# sdram_uni.net
KiCad netlist of a schematic drawn in Altium Designer
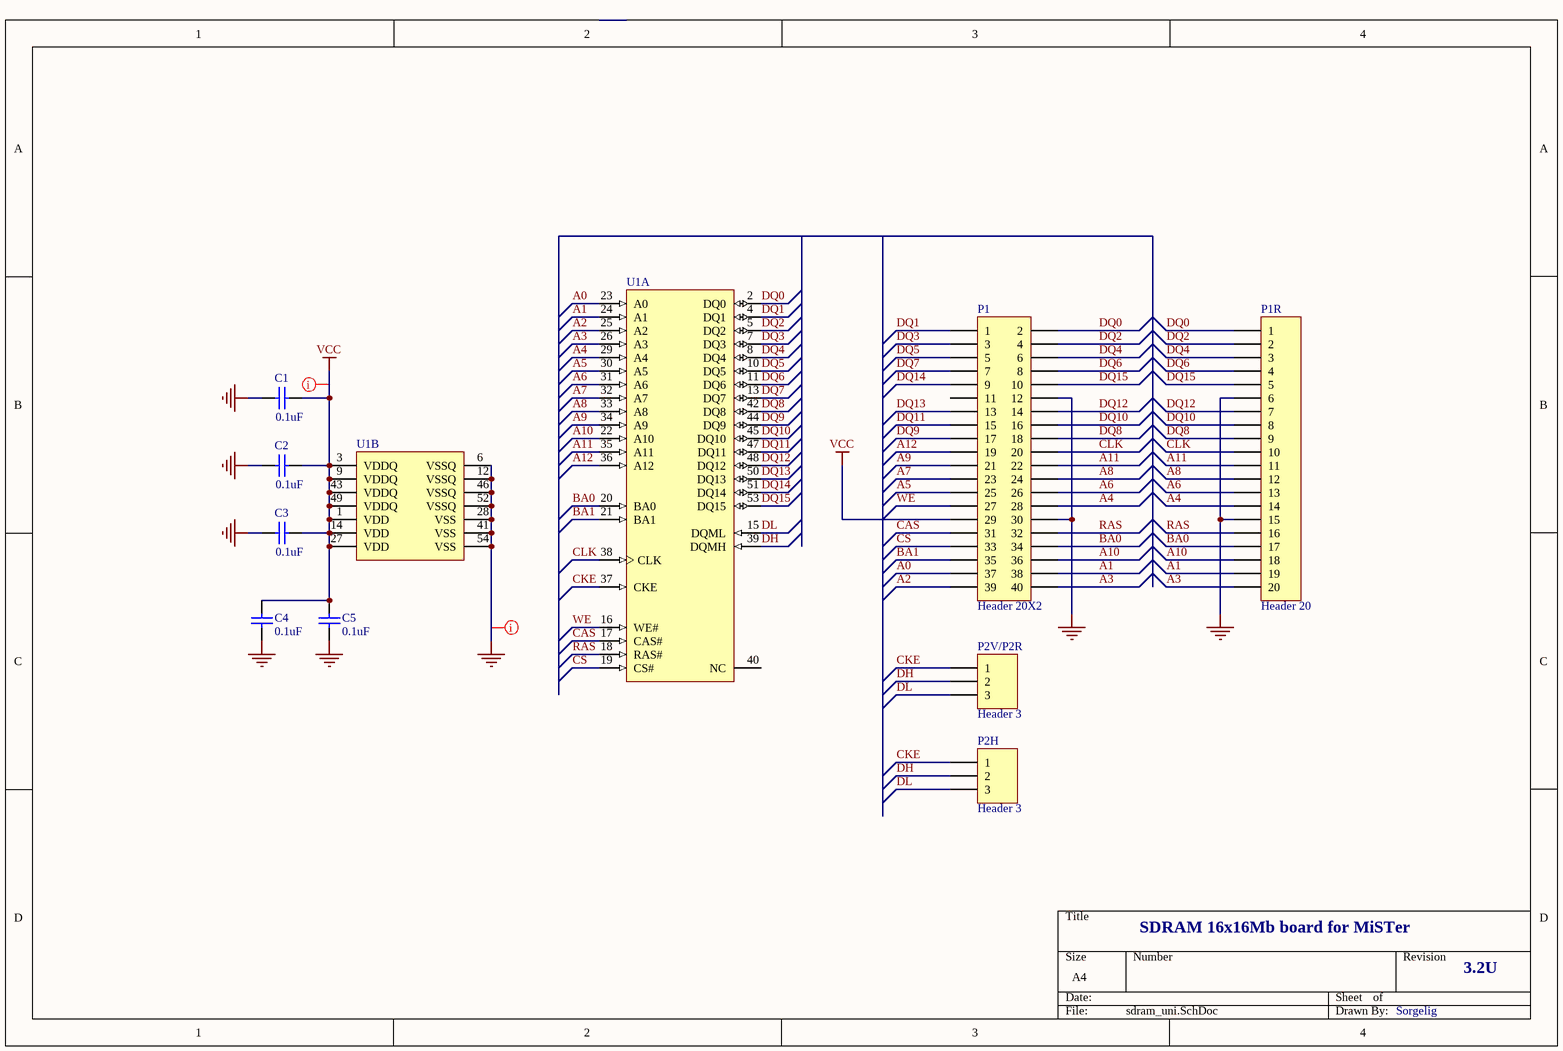
[diagram p0: sdram_uni.SchDoc]

(export (version "E")
  (design (tool "Eeschema 10.0.6"))
  (components
    (comp (ref "C1")
      (value "0.1uF")
      (footprint "C0805")
      (description "Ceramic Chip Capacitor - Standard")
      (fields (field (name "Comment") "C0805") (field (name "PUBLISHER") "Altium Limited"))
      (libsource (lib "lib") (part "C0805"))
    )
    (comp (ref "C2")
      (value "0.1uF")
      (footprint "C0805")
      (description "Ceramic Chip Capacitor - Standard")
      (fields (field (name "Comment") "C0805") (field (name "PUBLISHER") "Altium Limited"))
      (libsource (lib "lib") (part "C0805"))
    )
    (comp (ref "C3")
      (value "0.1uF")
      (footprint "C0805")
      (description "Ceramic Chip Capacitor - Standard")
      (fields (field (name "Comment") "+") (field (name "PUBLISHER") "Altium Limited"))
      (libsource (lib "lib") (part "C0805"))
    )
    (comp (ref "C4")
      (value "0.1uF")
      (footprint "C0805")
      (description "Ceramic Chip Capacitor - Standard")
      (fields (field (name "Comment") "C0805") (field (name "PUBLISHER") "Altium Limited"))
      (libsource (lib "lib") (part "C0805"))
    )
    (comp (ref "C5")
      (value "0.1uF")
      (footprint "C0805")
      (description "Ceramic Chip Capacitor - Standard")
      (fields (field (name "Comment") "+") (field (name "PUBLISHER") "Altium Limited"))
      (libsource (lib "lib") (part "C0805"))
    )
    (comp (ref "P1")
      (value "Header 20X2")
      (footprint "HDR20x2_90")
      (description "Header, 20-Pin, Dual row")
      (fields (field (name "PUBLISHER") "Altium Limited"))
      (libsource (lib "Miscellaneous Connectors") (part "Header 20X2"))
    )
    (comp (ref "P1R")
      (value "Header 20")
      (footprint "HDR1X20")
      (description "Header, 20-Pin")
      (fields (field (name "PUBLISHER") "Altium Limited"))
      (libsource (lib "Miscellaneous Connectors") (part "Header 20"))
    )
    (comp (ref "P2H")
      (value "Header 3")
      (footprint "HDR1X3")
      (description "Header, 3-Pin")
      (fields (field (name "PUBLISHER") "Altium Limited"))
      (libsource (lib "Miscellaneous Connectors") (part "Header 3"))
    )
    (comp (ref "P2V/P2R")
      (value "Header 3")
      (footprint "HDR1X3")
      (description "Header, 3-Pin")
      (fields (field (name "PUBLISHER") "Altium Limited"))
      (libsource (lib "Miscellaneous Connectors") (part "Header 3"))
    )
    (comp (ref "U1")
      (value "~")
      (footprint "TSOP54")
      (description "256Mb SDR SDRAM, 16Mb x 16, 6ns, 3.3V, 54-Pin TSOP")
      (fields (field (name "VOLTAGE") "3.3V ") (field (name "MANUFACTURER") "Micron"))
      (libsource (lib "lib") (part "AS4C16M16SA-6TCN"))
    )
  )
  (nets
    (net (code "1") (name "/A0") (class "Default")
      (node (ref "P1") (pin "37") (pinfunction "37_37") (pintype "passive"))
      (node (ref "U1") (pin "23") (pinfunction "A0_23") (pintype "input"))
    )
    (net (code "2") (name "/A1") (class "Default")
      (node (ref "P1") (pin "38") (pinfunction "38_38") (pintype "passive"))
      (node (ref "P1R") (pin "19") (pinfunction "19_19") (pintype "passive"))
      (node (ref "U1") (pin "24") (pinfunction "A1_24") (pintype "input"))
    )
    (net (code "3") (name "/A2") (class "Default")
      (node (ref "P1") (pin "39") (pinfunction "39_39") (pintype "passive"))
      (node (ref "U1") (pin "25") (pinfunction "A2_25") (pintype "input"))
    )
    (net (code "4") (name "/A3") (class "Default")
      (node (ref "P1") (pin "40") (pinfunction "40_40") (pintype "passive"))
      (node (ref "P1R") (pin "20") (pinfunction "20_20") (pintype "passive"))
      (node (ref "U1") (pin "26") (pinfunction "A3_26") (pintype "input"))
    )
    (net (code "5") (name "/A4") (class "Default")
      (node (ref "P1") (pin "28") (pinfunction "28_28") (pintype "passive"))
      (node (ref "P1R") (pin "14") (pinfunction "14_14") (pintype "passive"))
      (node (ref "U1") (pin "29") (pinfunction "A4_29") (pintype "input"))
    )
    (net (code "6") (name "/A5") (class "Default")
      (node (ref "P1") (pin "25") (pinfunction "25_25") (pintype "passive"))
      (node (ref "U1") (pin "30") (pinfunction "A5_30") (pintype "input"))
    )
    (net (code "7") (name "/A6") (class "Default")
      (node (ref "P1") (pin "26") (pinfunction "26_26") (pintype "passive"))
      (node (ref "P1R") (pin "13") (pinfunction "13_13") (pintype "passive"))
      (node (ref "U1") (pin "31") (pinfunction "A6_31") (pintype "input"))
    )
    (net (code "8") (name "/A7") (class "Default")
      (node (ref "P1") (pin "23") (pinfunction "23_23") (pintype "passive"))
      (node (ref "U1") (pin "32") (pinfunction "A7_32") (pintype "input"))
    )
    (net (code "9") (name "/A8") (class "Default")
      (node (ref "P1") (pin "24") (pinfunction "24_24") (pintype "passive"))
      (node (ref "P1R") (pin "12") (pinfunction "12_12") (pintype "passive"))
      (node (ref "U1") (pin "33") (pinfunction "A8_33") (pintype "input"))
    )
    (net (code "10") (name "/A9") (class "Default")
      (node (ref "P1") (pin "21") (pinfunction "21_21") (pintype "passive"))
      (node (ref "U1") (pin "34") (pinfunction "A9_34") (pintype "input"))
    )
    (net (code "11") (name "/A10") (class "Default")
      (node (ref "P1") (pin "36") (pinfunction "36_36") (pintype "passive"))
      (node (ref "P1R") (pin "18") (pinfunction "18_18") (pintype "passive"))
      (node (ref "U1") (pin "22") (pinfunction "A10_22") (pintype "input"))
    )
    (net (code "12") (name "/A11") (class "Default")
      (node (ref "P1") (pin "22") (pinfunction "22_22") (pintype "passive"))
      (node (ref "P1R") (pin "11") (pinfunction "11_11") (pintype "passive"))
      (node (ref "U1") (pin "35") (pinfunction "A11_35") (pintype "input"))
    )
    (net (code "13") (name "/A12") (class "Default")
      (node (ref "P1") (pin "19") (pinfunction "19_19") (pintype "passive"))
      (node (ref "U1") (pin "36") (pinfunction "A12_36") (pintype "input"))
    )
    (net (code "14") (name "/BA0") (class "Default")
      (node (ref "P1") (pin "34") (pinfunction "34_34") (pintype "passive"))
      (node (ref "P1R") (pin "17") (pinfunction "17_17") (pintype "passive"))
      (node (ref "U1") (pin "20") (pinfunction "BA0_20") (pintype "input"))
    )
    (net (code "15") (name "/BA1") (class "Default")
      (node (ref "P1") (pin "35") (pinfunction "35_35") (pintype "passive"))
      (node (ref "U1") (pin "21") (pinfunction "BA1_21") (pintype "input"))
    )
    (net (code "16") (name "/CAS") (class "Default")
      (node (ref "P1") (pin "31") (pinfunction "31_31") (pintype "passive"))
      (node (ref "U1") (pin "17") (pinfunction "CAS#_17") (pintype "input"))
    )
    (net (code "17") (name "/CKE") (class "Default")
      (node (ref "P2H") (pin "1") (pinfunction "1_1") (pintype "passive"))
      (node (ref "P2V/P2R") (pin "1") (pinfunction "1_1") (pintype "passive"))
      (node (ref "U1") (pin "37") (pinfunction "CKE_37") (pintype "input"))
    )
    (net (code "18") (name "/CLK") (class "Default")
      (node (ref "P1") (pin "20") (pinfunction "20_20") (pintype "passive"))
      (node (ref "P1R") (pin "10") (pinfunction "10_10") (pintype "passive"))
      (node (ref "U1") (pin "38") (pinfunction "CLK_38") (pintype "input"))
    )
    (net (code "19") (name "/CS") (class "Default")
      (node (ref "P1") (pin "33") (pinfunction "33_33") (pintype "passive"))
      (node (ref "U1") (pin "19") (pinfunction "CS#_19") (pintype "input"))
    )
    (net (code "20") (name "/DH") (class "Default")
      (node (ref "P2H") (pin "2") (pinfunction "2_2") (pintype "passive"))
      (node (ref "P2V/P2R") (pin "2") (pinfunction "2_2") (pintype "passive"))
      (node (ref "U1") (pin "39") (pinfunction "DQMH_39") (pintype "input"))
    )
    (net (code "21") (name "/DL") (class "Default")
      (node (ref "P2H") (pin "3") (pinfunction "3_3") (pintype "passive"))
      (node (ref "P2V/P2R") (pin "3") (pinfunction "3_3") (pintype "passive"))
      (node (ref "U1") (pin "15") (pinfunction "DQML_15") (pintype "input"))
    )
    (net (code "22") (name "/DQ0") (class "Default")
      (node (ref "P1") (pin "2") (pinfunction "2_2") (pintype "passive"))
      (node (ref "P1R") (pin "1") (pinfunction "1_1") (pintype "passive"))
      (node (ref "U1") (pin "2") (pinfunction "DQ0_2") (pintype "bidirectional"))
    )
    (net (code "23") (name "/DQ1") (class "Default")
      (node (ref "P1") (pin "1") (pinfunction "1_1") (pintype "passive"))
      (node (ref "U1") (pin "4") (pinfunction "DQ1_4") (pintype "bidirectional"))
    )
    (net (code "24") (name "/DQ2") (class "Default")
      (node (ref "P1") (pin "4") (pinfunction "4_4") (pintype "passive"))
      (node (ref "P1R") (pin "2") (pinfunction "2_2") (pintype "passive"))
      (node (ref "U1") (pin "5") (pinfunction "DQ2_5") (pintype "bidirectional"))
    )
    (net (code "25") (name "/DQ3") (class "Default")
      (node (ref "P1") (pin "3") (pinfunction "3_3") (pintype "passive"))
      (node (ref "U1") (pin "7") (pinfunction "DQ3_7") (pintype "bidirectional"))
    )
    (net (code "26") (name "/DQ4") (class "Default")
      (node (ref "P1") (pin "6") (pinfunction "6_6") (pintype "passive"))
      (node (ref "P1R") (pin "3") (pinfunction "3_3") (pintype "passive"))
      (node (ref "U1") (pin "8") (pinfunction "DQ4_8") (pintype "bidirectional"))
    )
    (net (code "27") (name "/DQ5") (class "Default")
      (node (ref "P1") (pin "5") (pinfunction "5_5") (pintype "passive"))
      (node (ref "U1") (pin "10") (pinfunction "DQ5_10") (pintype "bidirectional"))
    )
    (net (code "28") (name "/DQ6") (class "Default")
      (node (ref "P1") (pin "8") (pinfunction "8_8") (pintype "passive"))
      (node (ref "P1R") (pin "4") (pinfunction "4_4") (pintype "passive"))
      (node (ref "U1") (pin "11") (pinfunction "DQ6_11") (pintype "bidirectional"))
    )
    (net (code "29") (name "/DQ7") (class "Default")
      (node (ref "P1") (pin "7") (pinfunction "7_7") (pintype "passive"))
      (node (ref "U1") (pin "13") (pinfunction "DQ7_13") (pintype "bidirectional"))
    )
    (net (code "30") (name "/DQ8") (class "Default")
      (node (ref "P1") (pin "18") (pinfunction "18_18") (pintype "passive"))
      (node (ref "P1R") (pin "9") (pinfunction "9_9") (pintype "passive"))
      (node (ref "U1") (pin "42") (pinfunction "DQ8_42") (pintype "bidirectional"))
    )
    (net (code "31") (name "/DQ9") (class "Default")
      (node (ref "P1") (pin "17") (pinfunction "17_17") (pintype "passive"))
      (node (ref "U1") (pin "44") (pinfunction "DQ9_44") (pintype "bidirectional"))
    )
    (net (code "32") (name "/DQ10") (class "Default")
      (node (ref "P1") (pin "16") (pinfunction "16_16") (pintype "passive"))
      (node (ref "P1R") (pin "8") (pinfunction "8_8") (pintype "passive"))
      (node (ref "U1") (pin "45") (pinfunction "DQ10_45") (pintype "bidirectional"))
    )
    (net (code "33") (name "/DQ11") (class "Default")
      (node (ref "P1") (pin "15") (pinfunction "15_15") (pintype "passive"))
      (node (ref "U1") (pin "47") (pinfunction "DQ11_47") (pintype "bidirectional"))
    )
    (net (code "34") (name "/DQ12") (class "Default")
      (node (ref "P1") (pin "14") (pinfunction "14_14") (pintype "passive"))
      (node (ref "P1R") (pin "7") (pinfunction "7_7") (pintype "passive"))
      (node (ref "U1") (pin "48") (pinfunction "DQ12_48") (pintype "bidirectional"))
    )
    (net (code "35") (name "/DQ13") (class "Default")
      (node (ref "P1") (pin "13") (pinfunction "13_13") (pintype "passive"))
      (node (ref "U1") (pin "50") (pinfunction "DQ13_50") (pintype "bidirectional"))
    )
    (net (code "36") (name "/DQ14") (class "Default")
      (node (ref "P1") (pin "9") (pinfunction "9_9") (pintype "passive"))
      (node (ref "U1") (pin "51") (pinfunction "DQ14_51") (pintype "bidirectional"))
    )
    (net (code "37") (name "/DQ15") (class "Default")
      (node (ref "P1") (pin "10") (pinfunction "10_10") (pintype "passive"))
      (node (ref "P1R") (pin "5") (pinfunction "5_5") (pintype "passive"))
      (node (ref "U1") (pin "53") (pinfunction "DQ15_53") (pintype "bidirectional"))
    )
    (net (code "38") (name "/RAS") (class "Default")
      (node (ref "P1") (pin "32") (pinfunction "32_32") (pintype "passive"))
      (node (ref "P1R") (pin "16") (pinfunction "16_16") (pintype "passive"))
      (node (ref "U1") (pin "18") (pinfunction "RAS#_18") (pintype "input"))
    )
    (net (code "39") (name "/WE") (class "Default")
      (node (ref "P1") (pin "27") (pinfunction "27_27") (pintype "passive"))
      (node (ref "U1") (pin "16") (pinfunction "WE#_16") (pintype "input"))
    )
    (net (code "40") (name "GND") (class "Default")
      (node (ref "C1") (pin "1") (pinfunction "1_1") (pintype "passive"))
      (node (ref "C2") (pin "1") (pinfunction "1_1") (pintype "passive"))
      (node (ref "C3") (pin "1") (pinfunction "1_1") (pintype "passive"))
      (node (ref "C4") (pin "1") (pinfunction "1_1") (pintype "passive"))
      (node (ref "C5") (pin "1") (pinfunction "1_1") (pintype "passive"))
      (node (ref "P1") (pin "12") (pinfunction "12_12") (pintype "power_in"))
      (node (ref "P1") (pin "30") (pinfunction "30_30") (pintype "power_in"))
      (node (ref "P1R") (pin "15") (pinfunction "15_15") (pintype "passive"))
      (node (ref "P1R") (pin "6") (pinfunction "6_6") (pintype "passive"))
      (node (ref "U1") (pin "12") (pinfunction "VSSQ_12") (pintype "power_in"))
      (node (ref "U1") (pin "28") (pinfunction "VSS_28") (pintype "power_in"))
      (node (ref "U1") (pin "41") (pinfunction "VSS_41") (pintype "power_in"))
      (node (ref "U1") (pin "46") (pinfunction "VSSQ_46") (pintype "power_in"))
      (node (ref "U1") (pin "52") (pinfunction "VSSQ_52") (pintype "power_in"))
      (node (ref "U1") (pin "54") (pinfunction "VSS_54") (pintype "power_in"))
      (node (ref "U1") (pin "6") (pinfunction "VSSQ_6") (pintype "power_in"))
    )
    (net (code "41") (name "VCC") (class "Default")
      (node (ref "C1") (pin "2") (pinfunction "2_2") (pintype "passive"))
      (node (ref "C2") (pin "2") (pinfunction "2_2") (pintype "passive"))
      (node (ref "C3") (pin "2") (pinfunction "2_2") (pintype "passive"))
      (node (ref "C4") (pin "2") (pinfunction "2_2") (pintype "passive"))
      (node (ref "C5") (pin "2") (pinfunction "2_2") (pintype "passive"))
      (node (ref "P1") (pin "29") (pinfunction "29_29") (pintype "power_in"))
      (node (ref "U1") (pin "1") (pinfunction "VDD_1") (pintype "power_in"))
      (node (ref "U1") (pin "14") (pinfunction "VDD_14") (pintype "power_in"))
      (node (ref "U1") (pin "27") (pinfunction "VDD_27") (pintype "power_in"))
      (node (ref "U1") (pin "3") (pinfunction "VDDQ_3") (pintype "power_in"))
      (node (ref "U1") (pin "43") (pinfunction "VDDQ_43") (pintype "power_in"))
      (node (ref "U1") (pin "49") (pinfunction "VDDQ_49") (pintype "power_in"))
      (node (ref "U1") (pin "9") (pinfunction "VDDQ_9") (pintype "power_in"))
    )
    (net (code "42") (name "unconnected-(P1-Pad11)") (class "Default")
      (node (ref "P1") (pin "11") (pinfunction "11_11") (pintype "power_in"))
    )
    (net (code "43") (name "unconnected-(U1A-NC-Pad40)") (class "Default")
      (node (ref "U1") (pin "40") (pinfunction "NC_40") (pintype "passive"))
    )
  )
)
